# HM-RC-8_Remote-v01-001.net
KiCad netlist of a schematic drawn in EAGLE
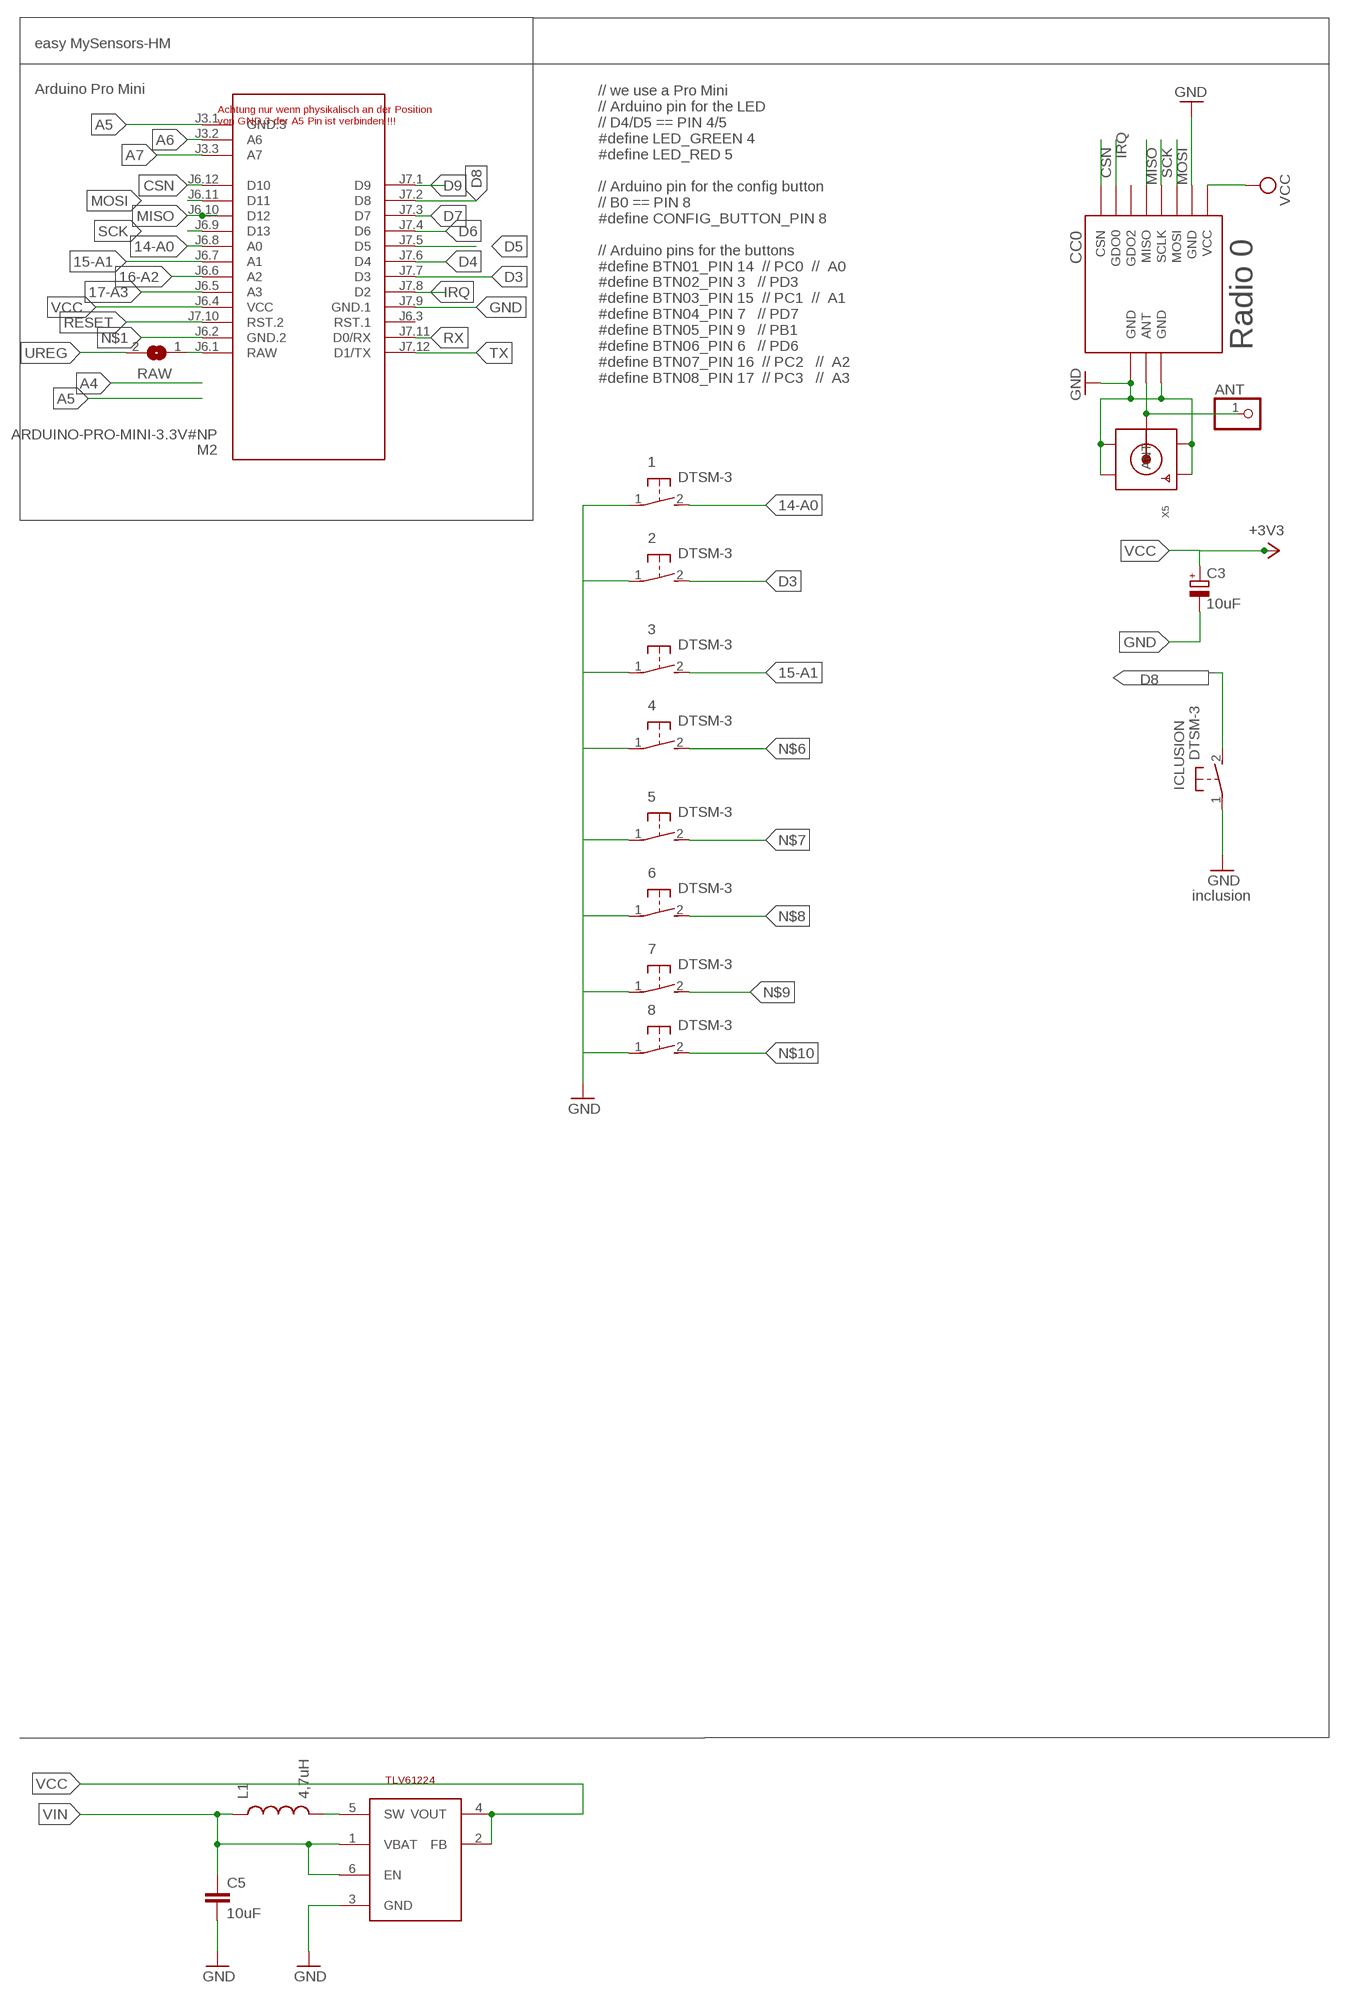
[diagram p0: schematic, sheet 1]

(export (version "E")
  (design (tool "Eeschema 10.0.6"))
  (components
    (comp (ref "1")
      (value "DTSM-3")
      (footprint "eagle-import:DTSM-3")
      (libsource (lib "eagle-import") (part "DTSM-3"))
    )
    (comp (ref "2")
      (value "DTSM-3")
      (footprint "eagle-import:DTSM-3")
      (libsource (lib "eagle-import") (part "DTSM-3"))
    )
    (comp (ref "3")
      (value "DTSM-3")
      (footprint "eagle-import:DTSM-3")
      (libsource (lib "eagle-import") (part "DTSM-3"))
    )
    (comp (ref "4")
      (value "DTSM-3")
      (footprint "eagle-import:DTSM-3")
      (libsource (lib "eagle-import") (part "DTSM-3"))
    )
    (comp (ref "5")
      (value "DTSM-3")
      (footprint "eagle-import:DTSM-3")
      (libsource (lib "eagle-import") (part "DTSM-3"))
    )
    (comp (ref "6")
      (value "DTSM-3")
      (footprint "eagle-import:DTSM-3")
      (libsource (lib "eagle-import") (part "DTSM-3"))
    )
    (comp (ref "7")
      (value "DTSM-3")
      (footprint "eagle-import:DTSM-3")
      (libsource (lib "eagle-import") (part "DTSM-3"))
    )
    (comp (ref "8")
      (value "DTSM-3")
      (footprint "eagle-import:DTSM-3")
      (libsource (lib "eagle-import") (part "DTSM-3"))
    )
    (comp (ref "ANT")
      (value "PINHD-1X1")
      (footprint "eagle-import:1X01")
      (libsource (lib "eagle-import") (part "PINHD-1X1"))
    )
    (comp (ref "C3")
      (value "10uF")
      (footprint "eagle-import:SMC_C")
      (libsource (lib "eagle-import") (part "CPOL-EUSMCC"))
    )
    (comp (ref "C5")
      (value "10uF")
      (footprint "eagle-import:0805")
      (libsource (lib "eagle-import") (part "CAP0805"))
    )
    (comp (ref "CC0")
      (value "CC1101")
      (footprint "eagle-import:CC1101_MODULE1_SMD")
      (libsource (lib "eagle-import") (part "CC1101_MODULE1SMD"))
    )
    (comp (ref "ICLUSION")
      (value "DTSM-3")
      (footprint "eagle-import:DTSM-3")
      (libsource (lib "eagle-import") (part "DTSM-3"))
    )
    (comp (ref "L1")
      (value "4,7uH")
      (footprint "eagle-import:0805")
      (libsource (lib "eagle-import") (part "INDUCTOR0805"))
    )
    (comp (ref "M2")
      (value "ARDUINO-PRO-MINI-3.3V#NP")
      (footprint "eagle-import:ARDUINO-PRO-MINI#NP")
      (libsource (lib "eagle-import") (part "ARDUINO-PRO-MINI-#NP3.3V"))
    )
    (comp (ref "RAW") (value "SJ") (footprint "eagle-import:SJ") (libsource (lib "eagle-import") (part "SJ")))
    (comp (ref "STEPUP")
      (value "TLV61224")
      (footprint "eagle-import:SOT23-6L")
      (libsource (lib "eagle-import") (part "TI-TLV61224"))
    )
    (comp (ref "X5")
      (value "SMACONNECTOR_EDGE")
      (footprint "eagle-import:SMA_EDGELAUNCH")
      (libsource (lib "eagle-import") (part "SMACONNECTOR_EDGE"))
    )
  )
  (nets
    (net (code "1") (name "14-A0") (class "Default")
      (node (ref "1") (pin "2") (pinfunction "2_2") (pintype "passive"))
      (node (ref "M2") (pin "J6.8") (pinfunction "A0_J6.8") (pintype "bidirectional"))
    )
    (net (code "2") (name "15-A1") (class "Default")
      (node (ref "3") (pin "2") (pinfunction "2_2") (pintype "passive"))
      (node (ref "M2") (pin "J6.7") (pinfunction "A1_J6.7") (pintype "bidirectional"))
    )
    (net (code "3") (name "16-A2") (class "Default")
      (node (ref "M2") (pin "J6.6") (pinfunction "A2_J6.6") (pintype "bidirectional"))
    )
    (net (code "4") (name "17-A3") (class "Default")
      (node (ref "M2") (pin "J6.5") (pinfunction "A3_J6.5") (pintype "bidirectional"))
    )
    (net (code "6") (name "A5") (class "Default")
      (node (ref "M2") (pin "J3.1") (pinfunction "GND.3_J3.1") (pintype "bidirectional"))
    )
    (net (code "7") (name "A6") (class "Default")
      (node (ref "M2") (pin "J3.2") (pinfunction "A6_J3.2") (pintype "bidirectional"))
    )
    (net (code "8") (name "A7") (class "Default")
      (node (ref "M2") (pin "J3.3") (pinfunction "A7_J3.3") (pintype "bidirectional"))
    )
    (net (code "9") (name "CSN") (class "Default")
      (node (ref "CC0") (pin "CSN") (pinfunction "CSN_CSN") (pintype "bidirectional"))
      (node (ref "M2") (pin "J6.12") (pinfunction "D10_J6.12") (pintype "bidirectional"))
    )
    (net (code "10") (name "D3") (class "Default")
      (node (ref "2") (pin "2") (pinfunction "2_2") (pintype "passive"))
      (node (ref "M2") (pin "J7.7") (pinfunction "D3_J7.7") (pintype "bidirectional"))
    )
    (net (code "11") (name "D4") (class "Default")
      (node (ref "M2") (pin "J7.6") (pinfunction "D4_J7.6") (pintype "bidirectional"))
    )
    (net (code "12") (name "D5") (class "Default")
      (node (ref "M2") (pin "J7.5") (pinfunction "D5_J7.5") (pintype "bidirectional"))
    )
    (net (code "13") (name "D6") (class "Default")
      (node (ref "M2") (pin "J7.4") (pinfunction "D6_J7.4") (pintype "bidirectional"))
    )
    (net (code "14") (name "D7") (class "Default")
      (node (ref "M2") (pin "J7.3") (pinfunction "D7_J7.3") (pintype "bidirectional"))
    )
    (net (code "15") (name "D8") (class "Default")
      (node (ref "ICLUSION") (pin "2") (pinfunction "2_2") (pintype "passive"))
      (node (ref "M2") (pin "J7.2") (pinfunction "D8_J7.2") (pintype "bidirectional"))
    )
    (net (code "16") (name "D9") (class "Default")
      (node (ref "M2") (pin "J7.1") (pinfunction "D9_J7.1") (pintype "bidirectional"))
    )
    (net (code "17") (name "GND") (class "Default")
      (node (ref "1") (pin "1") (pinfunction "1_1") (pintype "passive"))
      (node (ref "3") (pin "1") (pinfunction "1_1") (pintype "passive"))
      (node (ref "4") (pin "1") (pinfunction "1_1") (pintype "passive"))
      (node (ref "5") (pin "1") (pinfunction "1_1") (pintype "passive"))
      (node (ref "6") (pin "1") (pinfunction "1_1") (pintype "passive"))
      (node (ref "7") (pin "1") (pinfunction "1_1") (pintype "passive"))
      (node (ref "8") (pin "1") (pinfunction "1_1") (pintype "passive"))
      (node (ref "C3") (pin "-") (pinfunction "-_-") (pintype "passive"))
      (node (ref "C5") (pin "2") (pinfunction "2_2") (pintype "passive"))
      (node (ref "CC0") (pin "GND@0") (pinfunction "GND_GND@0") (pintype "power_in"))
      (node (ref "CC0") (pin "GND@1") (pinfunction "GND_GND@1") (pintype "power_in"))
      (node (ref "CC0") (pin "GND@2") (pinfunction "GND_GND@2") (pintype "power_in"))
      (node (ref "ICLUSION") (pin "1") (pinfunction "1_1") (pintype "passive"))
      (node (ref "M2") (pin "J7.9") (pinfunction "GND.1_J7.9") (pintype "power_in"))
      (node (ref "STEPUP") (pin "3") (pinfunction "GND_3") (pintype "power_in"))
      (node (ref "X5") (pin "GND@1") (pinfunction "GND4_GND@1") (pintype "power_in"))
      (node (ref "X5") (pin "GND@2") (pinfunction "GND3_GND@2") (pintype "power_in"))
      (node (ref "X5") (pin "GND@3") (pinfunction "GND2_GND@3") (pintype "power_in"))
      (node (ref "X5") (pin "GND@4") (pinfunction "GND1_GND@4") (pintype "power_in"))
    )
    (net (code "18") (name "IRQ") (class "Default")
      (node (ref "CC0") (pin "GDO0") (pinfunction "GDO0_GDO0") (pintype "bidirectional"))
      (node (ref "M2") (pin "J7.8") (pinfunction "D2_J7.8") (pintype "bidirectional"))
    )
    (net (code "19") (name "MISO") (class "Default")
      (node (ref "CC0") (pin "MISO") (pinfunction "MISO_MISO") (pintype "bidirectional"))
      (node (ref "M2") (pin "J6.10") (pinfunction "D12_J6.10") (pintype "bidirectional"))
    )
    (net (code "20") (name "MOSI") (class "Default")
      (node (ref "CC0") (pin "MOSI") (pinfunction "MOSI_MOSI") (pintype "bidirectional"))
      (node (ref "M2") (pin "J6.11") (pinfunction "D11_J6.11") (pintype "bidirectional"))
    )
    (net (code "21") (name "N$1") (class "Default")
      (node (ref "M2") (pin "J6.2") (pinfunction "GND.2_J6.2") (pintype "power_in"))
    )
    (net (code "22") (name "N$6") (class "Default")
      (node (ref "4") (pin "2") (pinfunction "2_2") (pintype "passive"))
    )
    (net (code "23") (name "N$7") (class "Default")
      (node (ref "5") (pin "2") (pinfunction "2_2") (pintype "passive"))
    )
    (net (code "24") (name "N$8") (class "Default")
      (node (ref "6") (pin "2") (pinfunction "2_2") (pintype "passive"))
    )
    (net (code "25") (name "N$9") (class "Default")
      (node (ref "7") (pin "2") (pinfunction "2_2") (pintype "passive"))
    )
    (net (code "26") (name "N$10") (class "Default")
      (node (ref "8") (pin "2") (pinfunction "2_2") (pintype "passive"))
    )
    (net (code "27") (name "Net-(M2-RAW)") (class "Default")
      (node (ref "M2") (pin "J6.1") (pinfunction "RAW_J6.1") (pintype "power_in"))
      (node (ref "RAW") (pin "1") (pinfunction "1_1") (pintype "passive"))
    )
    (net (code "28") (name "Net-(STEPUP-SW)") (class "Default")
      (node (ref "L1") (pin "2") (pinfunction "2_2") (pintype "passive"))
      (node (ref "STEPUP") (pin "5") (pinfunction "SW_5") (pintype "power_in"))
    )
    (net (code "29") (name "Net-(X5-ANT)") (class "Default")
      (node (ref "ANT") (pin "1") (pinfunction "1_1") (pintype "passive"))
      (node (ref "CC0") (pin "ANT") (pinfunction "ANT_ANT") (pintype "output"))
      (node (ref "X5") (pin "P") (pinfunction "ANT_P") (pintype "bidirectional"))
    )
    (net (code "30") (name "RESET") (class "Default")
      (node (ref "M2") (pin "J7.10") (pinfunction "RST.2_J7.10") (pintype "bidirectional"))
    )
    (net (code "31") (name "RX") (class "Default")
      (node (ref "M2") (pin "J7.11") (pinfunction "D0/RX_J7.11") (pintype "bidirectional"))
    )
    (net (code "32") (name "SCK") (class "Default")
      (node (ref "CC0") (pin "SCLK") (pinfunction "SCLK_SCLK") (pintype "bidirectional"))
      (node (ref "M2") (pin "J6.9") (pinfunction "D13_J6.9") (pintype "bidirectional"))
    )
    (net (code "33") (name "TX") (class "Default")
      (node (ref "M2") (pin "J7.12") (pinfunction "D1/TX_J7.12") (pintype "bidirectional"))
    )
    (net (code "34") (name "UREG") (class "Default")
      (node (ref "RAW") (pin "2") (pinfunction "2_2") (pintype "passive"))
    )
    (net (code "35") (name "VCC") (class "Default")
      (node (ref "C3") (pin "+") (pinfunction "+_+") (pintype "passive"))
      (node (ref "CC0") (pin "VCC") (pinfunction "VCC_VCC") (pintype "power_in"))
      (node (ref "M2") (pin "J6.4") (pinfunction "VCC_J6.4") (pintype "power_in"))
      (node (ref "STEPUP") (pin "2") (pinfunction "FB_2") (pintype "input"))
      (node (ref "STEPUP") (pin "4") (pinfunction "VOUT_4") (pintype "power_in"))
    )
    (net (code "36") (name "VIN") (class "Default")
      (node (ref "C5") (pin "1") (pinfunction "1_1") (pintype "passive"))
      (node (ref "L1") (pin "1") (pinfunction "1_1") (pintype "passive"))
      (node (ref "STEPUP") (pin "1") (pinfunction "VBAT_1") (pintype "power_in"))
      (node (ref "STEPUP") (pin "6") (pinfunction "EN_6") (pintype "input"))
    )
    (net (code "37") (name "unconnected-(2-Pad1)") (class "Default")
      (node (ref "2") (pin "1") (pinfunction "1_1") (pintype "passive"))
    )
    (net (code "38") (name "unconnected-(CC0-PadGDO2)") (class "Default")
      (node (ref "CC0") (pin "GDO2") (pinfunction "GDO2_GDO2") (pintype "bidirectional"))
    )
    (net (code "39") (name "unconnected-(M2-RST.1-PadJ6.3)") (class "Default")
      (node (ref "M2") (pin "J6.3") (pinfunction "RST.1_J6.3") (pintype "bidirectional"))
    )
  )
)
